# BoardB-Input.net
KiCad netlist of a schematic drawn in Altium Designer
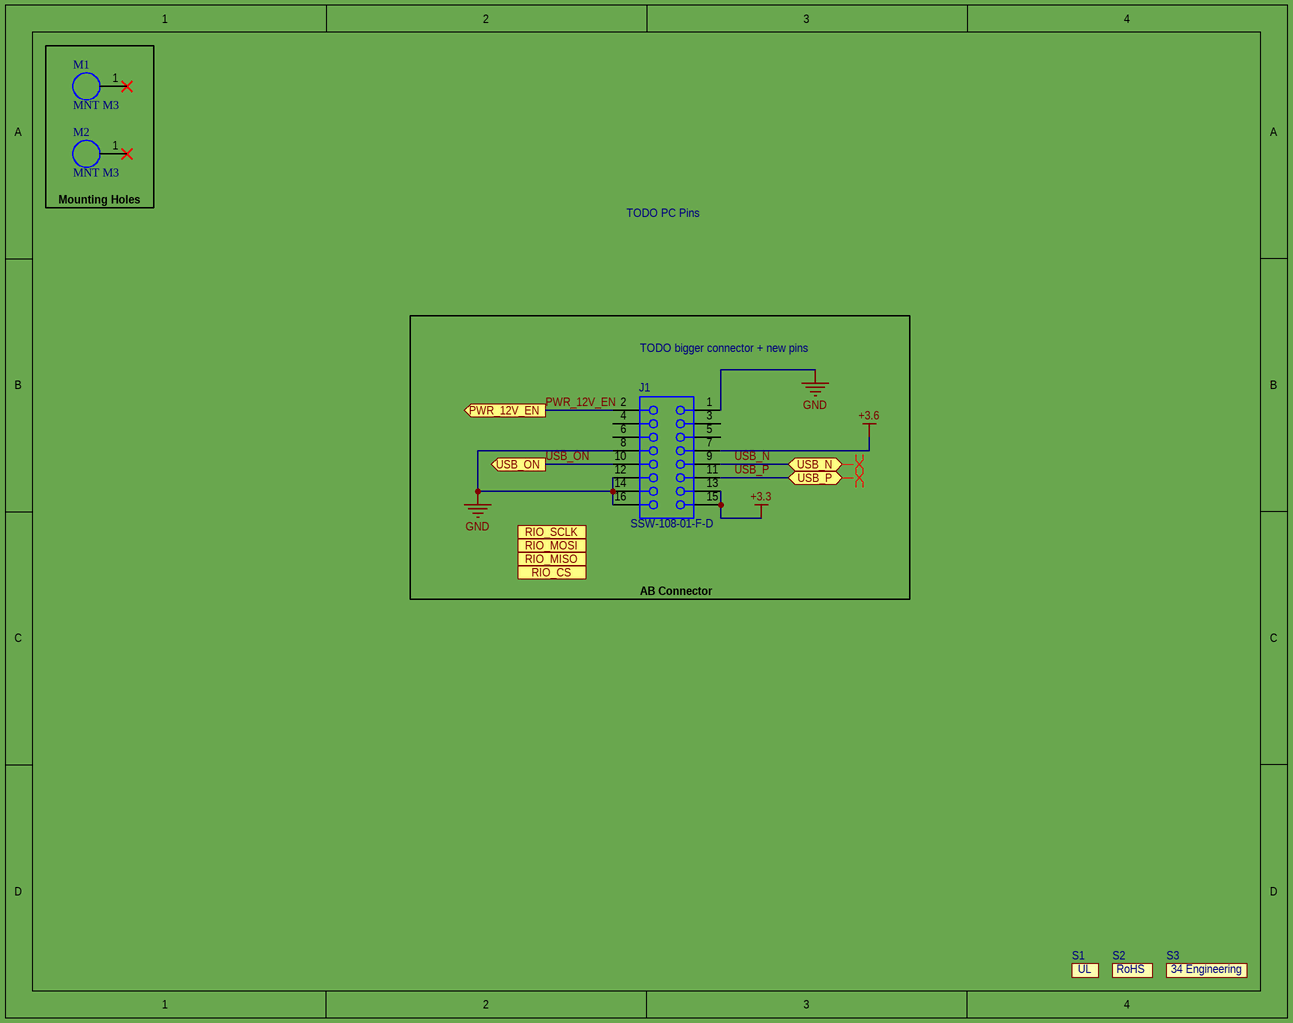
[diagram p0: BoardB-Input.SchDoc]

(export (version "E")
  (design (tool "Eeschema 10.0.6"))
  (components
    (comp (ref "J1")
      (value "SSW-108-01-F-D")
      (footprint "SMTC-SSW-108-01-X-D")
      (description "SQ Post Socket, Through-hole, Vertical, -55 to 125 degC, 2.54mm Pitch, 16-Pin, Female, RoHS")
      (fields (field (name "MANUFACTURER") "Samtec"))
      (libsource (lib "Altium Content Vault") (part "SMTC-SSW-108-X-X-D-X"))
    )
    (comp (ref "M1")
      (value "MNT M3")
      (footprint "MNT M3")
      (description "Mounting hole for an M3 bolt")
      (libsource (lib "Virtex") (part "MNT M3"))
    )
    (comp (ref "M2")
      (value "MNT M3")
      (footprint "MNT M3")
      (description "Mounting hole for an M3 bolt")
      (libsource (lib "Virtex") (part "MNT M3"))
    )
    (comp (ref "S1") (value "~") (footprint "UL") (libsource (lib "Virtex") (part "UL")))
    (comp (ref "S2") (value "~") (footprint "RoHS") (libsource (lib "Virtex") (part "RoHS")))
    (comp (ref "S3")
      (value "~")
      (footprint "34EngineeringLogo")
      (description "34 Engineering Silkscreen Logo")
      (libsource (lib "Virtex") (part "34EngineeringLogo"))
    )
  )
  (nets
    (net (code "1") (name "+3.3") (class "Default")
      (node (ref "J1") (pin "13") (pinfunction "13_13") (pintype "passive"))
      (node (ref "J1") (pin "15") (pinfunction "15_15") (pintype "passive"))
    )
    (net (code "2") (name "+3.6") (class "Default")
      (node (ref "J1") (pin "7") (pinfunction "7_7") (pintype "passive"))
    )
    (net (code "3") (name "/PWR_12V_EN") (class "Default")
      (node (ref "J1") (pin "2") (pinfunction "2_2") (pintype "passive"))
    )
    (net (code "8") (name "/USB_N") (class "Default")
      (node (ref "J1") (pin "9") (pinfunction "9_9") (pintype "passive"))
    )
    (net (code "9") (name "/USB_ON") (class "Default")
      (node (ref "J1") (pin "10") (pinfunction "10_10") (pintype "passive"))
    )
    (net (code "10") (name "/USB_P") (class "Default")
      (node (ref "J1") (pin "11") (pinfunction "11_11") (pintype "passive"))
    )
    (net (code "11") (name "GND") (class "Default")
      (node (ref "J1") (pin "1") (pinfunction "1_1") (pintype "passive"))
      (node (ref "J1") (pin "12") (pinfunction "12_12") (pintype "passive"))
      (node (ref "J1") (pin "14") (pinfunction "14_14") (pintype "passive"))
      (node (ref "J1") (pin "16") (pinfunction "16_16") (pintype "passive"))
      (node (ref "J1") (pin "8") (pinfunction "8_8") (pintype "passive"))
    )
    (net (code "12") (name "unconnected-(J1-Pad3)") (class "Default")
      (node (ref "J1") (pin "3") (pinfunction "3_3") (pintype "passive"))
    )
    (net (code "13") (name "unconnected-(J1-Pad4)") (class "Default")
      (node (ref "J1") (pin "4") (pinfunction "4_4") (pintype "passive"))
    )
    (net (code "14") (name "unconnected-(J1-Pad5)") (class "Default")
      (node (ref "J1") (pin "5") (pinfunction "5_5") (pintype "passive"))
    )
    (net (code "15") (name "unconnected-(J1-Pad6)") (class "Default")
      (node (ref "J1") (pin "6") (pinfunction "6_6") (pintype "passive"))
    )
    (net (code "16") (name "unconnected-(M1-Pad1)") (class "Default")
      (node (ref "M1") (pin "1") (pintype "passive+no_connect"))
    )
    (net (code "17") (name "unconnected-(M2-Pad1)") (class "Default")
      (node (ref "M2") (pin "1") (pintype "passive+no_connect"))
    )
  )
)
